# connector_schematic-3.net
KiCad netlist of a schematic drawn in EAGLE
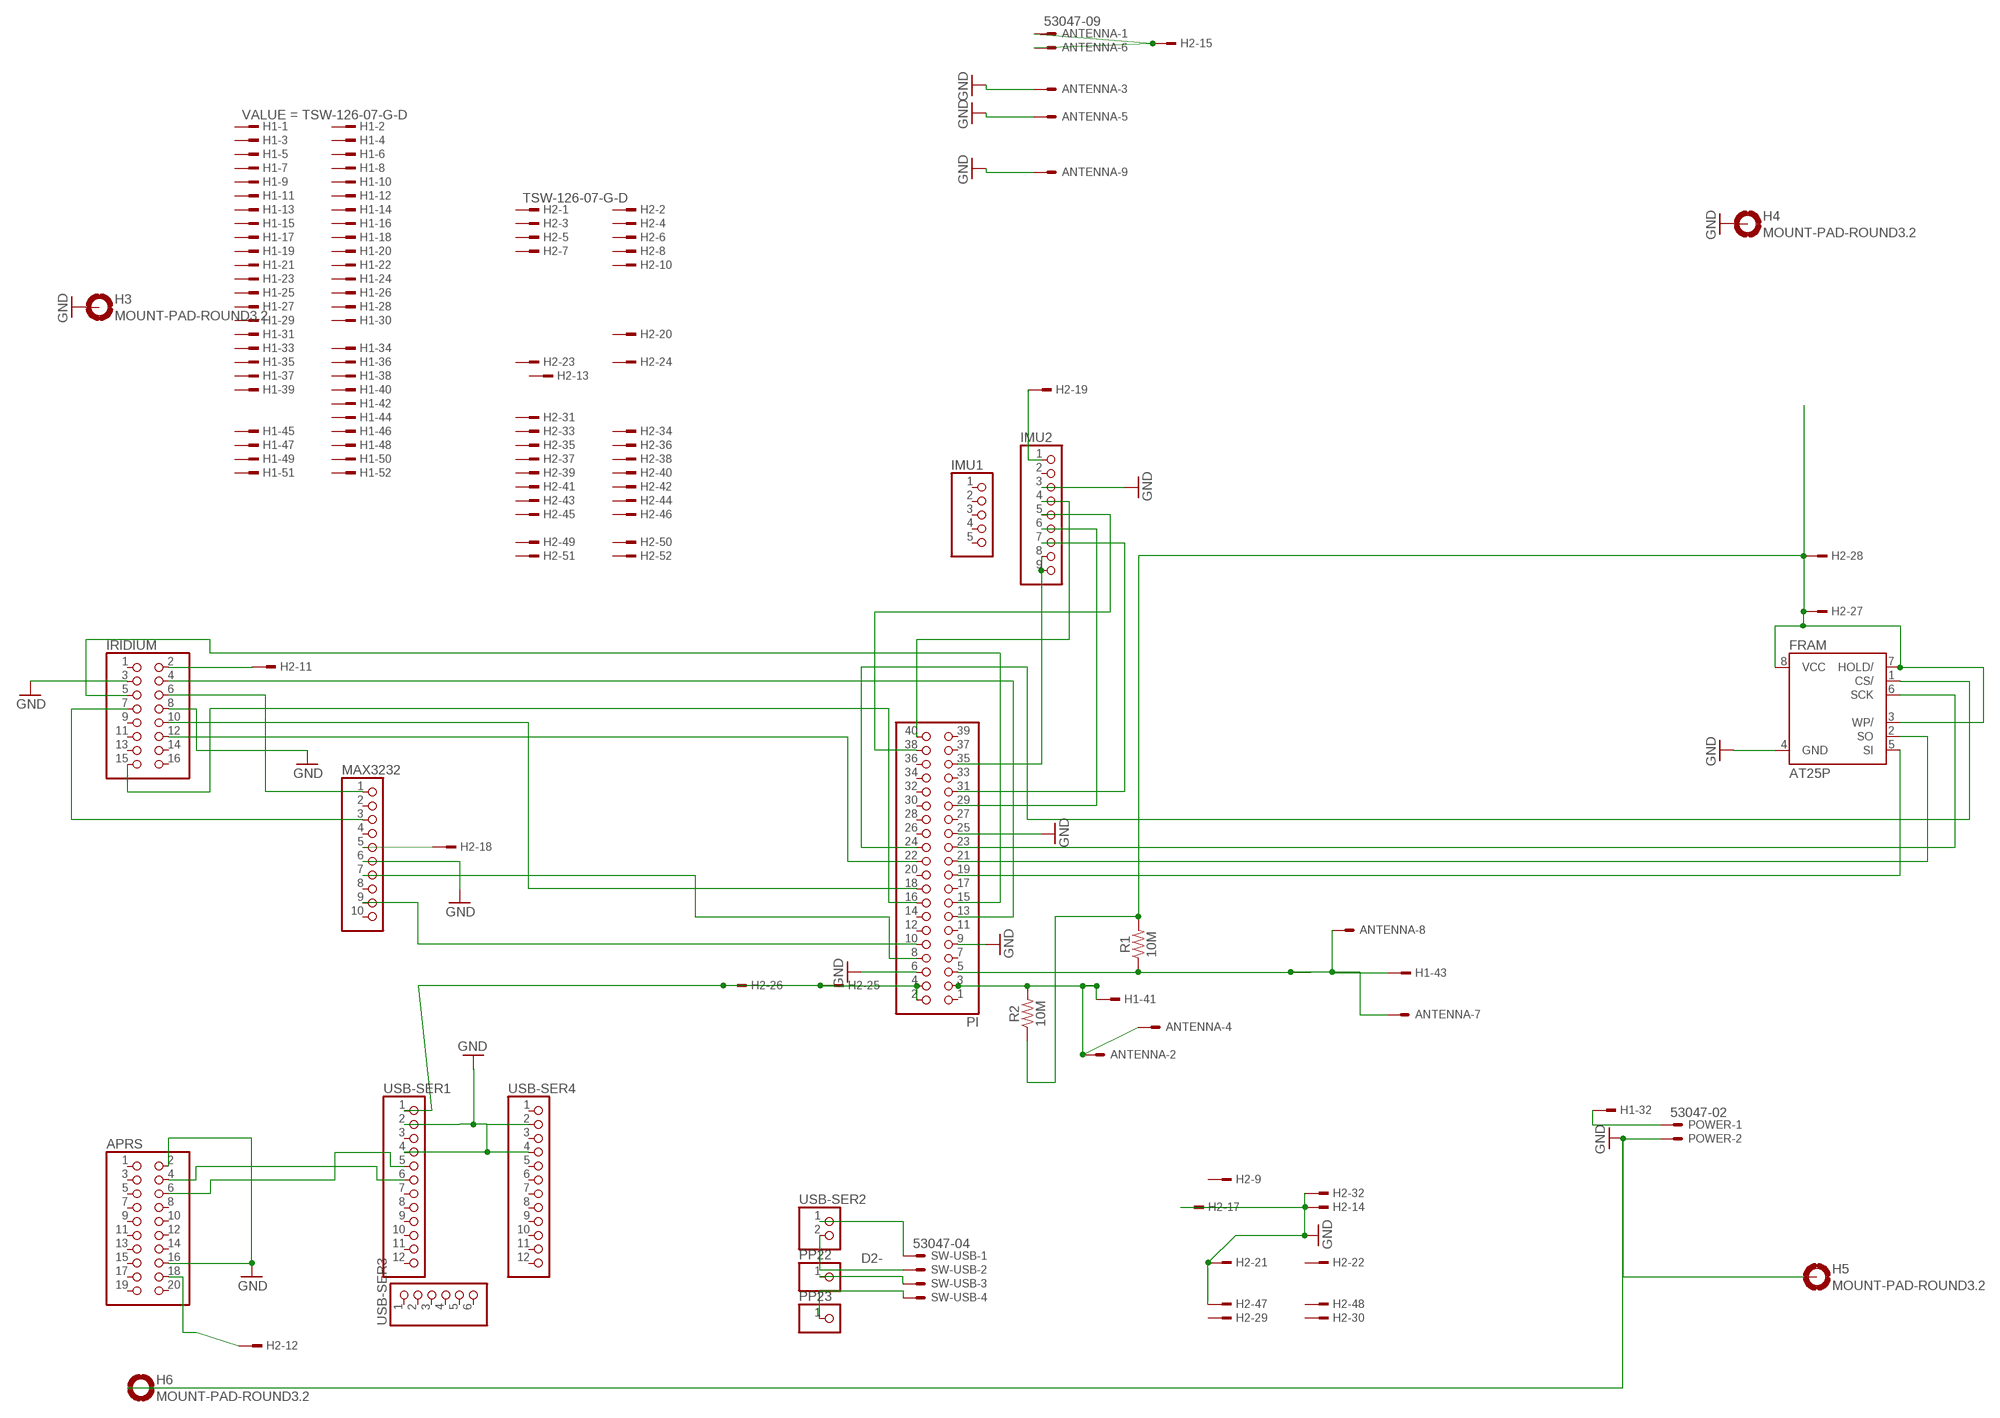
[diagram p0: schematic, sheet 1]

(export (version "E")
  (design (tool "Eeschema 10.0.6"))
  (components
    (comp (ref "ANTENNA")
      (value "53047-09")
      (footprint "eagle-import:53047-09")
      (fields (field (name "MF") "MOLEX") (field (name "MPN") "53047-0910"))
      (libsource (lib "eagle-import") (part "53?-09047"))
    )
    (comp (ref "APRS")
      (value "PINHD-2X10")
      (footprint "eagle-import:2X10")
      (libsource (lib "eagle-import") (part "PINHD-2X10"))
    )
    (comp (ref "FRAM")
      (value "AT25P")
      (footprint "eagle-import:DIL08")
      (fields (field (name "MPN") "CAT25040LI-G"))
      (libsource (lib "eagle-import") (part "AT25P"))
    )
    (comp (ref "H1")
      (value "TSW-126-07-G-D")
      (footprint "eagle-import:TSW-126-XX-G-D")
      (fields (field (name "MF") "Samtec Inc."))
      (libsource (lib "eagle-import") (part "TSW-126--G-D07"))
    )
    (comp (ref "H2")
      (value "TSW-126-07-G-D")
      (footprint "eagle-import:TSW-126-XX-G-D")
      (fields (field (name "MF") "Samtec Inc."))
      (libsource (lib "eagle-import") (part "TSW-126--G-D07"))
    )
    (comp (ref "H3")
      (value "MOUNT-PAD-ROUND3.2")
      (footprint "eagle-import:3,2-PAD")
      (libsource (lib "eagle-import") (part "MOUNT-PAD-ROUND3.2"))
    )
    (comp (ref "H4")
      (value "MOUNT-PAD-ROUND3.2")
      (footprint "eagle-import:3,2-PAD")
      (libsource (lib "eagle-import") (part "MOUNT-PAD-ROUND3.2"))
    )
    (comp (ref "H5")
      (value "MOUNT-PAD-ROUND3.2")
      (footprint "eagle-import:3,2-PAD")
      (libsource (lib "eagle-import") (part "MOUNT-PAD-ROUND3.2"))
    )
    (comp (ref "H6")
      (value "MOUNT-PAD-ROUND3.2")
      (footprint "eagle-import:3,2-PAD")
      (libsource (lib "eagle-import") (part "MOUNT-PAD-ROUND3.2"))
    )
    (comp (ref "IMU1")
      (value "PINHD-1X5")
      (footprint "eagle-import:1X05")
      (libsource (lib "eagle-import") (part "PINHD-1X5"))
    )
    (comp (ref "IMU2")
      (value "PINHD-1X9")
      (footprint "eagle-import:1X09")
      (libsource (lib "eagle-import") (part "PINHD-1X9"))
    )
    (comp (ref "IRIDIUM")
      (value "PINHD-2X8")
      (footprint "eagle-import:2X08")
      (libsource (lib "eagle-import") (part "PINHD-2X8"))
    )
    (comp (ref "MAX3232")
      (value "PINHD-1X10")
      (footprint "eagle-import:1X10")
      (libsource (lib "eagle-import") (part "PINHD-1X10"))
    )
    (comp (ref "PI")
      (value "PINHD-2X20")
      (footprint "eagle-import:2X20")
      (libsource (lib "eagle-import") (part "PINHD-2X20"))
    )
    (comp (ref "POWER")
      (value "53047-02")
      (footprint "eagle-import:53047-02")
      (fields (field (name "MF") "MOLEX") (field (name "MPN") "53047-0210"))
      (libsource (lib "eagle-import") (part "53?-02047"))
    )
    (comp (ref "PP22")
      (value "PINHD-1X1")
      (footprint "eagle-import:1X01")
      (libsource (lib "eagle-import") (part "PINHD-1X1"))
    )
    (comp (ref "PP23")
      (value "PINHD-1X1")
      (footprint "eagle-import:1X01")
      (libsource (lib "eagle-import") (part "PINHD-1X1"))
    )
    (comp (ref "R1")
      (value "10M")
      (footprint "eagle-import:AXIAL-0.3")
      (libsource (lib "eagle-import") (part "10MOHM-HORIZ-1/4W-5%"))
    )
    (comp (ref "R2")
      (value "10M")
      (footprint "eagle-import:AXIAL-0.3")
      (libsource (lib "eagle-import") (part "10MOHM-HORIZ-1/4W-5%"))
    )
    (comp (ref "SW-USB")
      (value "53047-04")
      (footprint "eagle-import:53047-04")
      (fields (field (name "MF") "WALDOM/MOLEX") (field (name "MPN") "53047-0410"))
      (libsource (lib "eagle-import") (part "53?-04047"))
    )
    (comp (ref "USB-SER1")
      (value "PINHD-1X12")
      (footprint "eagle-import:1X12")
      (libsource (lib "eagle-import") (part "PINHD-1X12"))
    )
    (comp (ref "USB-SER2")
      (value "PINHD-1X2")
      (footprint "eagle-import:1X02")
      (libsource (lib "eagle-import") (part "PINHD-1X2"))
    )
    (comp (ref "USB-SER3")
      (value "PINHD-1X6")
      (footprint "eagle-import:1X06")
      (libsource (lib "eagle-import") (part "PINHD-1X6"))
    )
    (comp (ref "USB-SER4")
      (value "PINHD-1X12")
      (footprint "eagle-import:1X12")
      (libsource (lib "eagle-import") (part "PINHD-1X12"))
    )
  )
  (nets
    (net (code "1") (name "/D2-") (class "Default")
      (node (ref "SW-USB") (pin "2") (pinfunction "S_2") (pintype "passive"))
      (node (ref "USB-SER2") (pin "2") (pinfunction "2_2") (pintype "passive"))
    )
    (net (code "2") (name "GND") (class "Default")
      (node (ref "ANTENNA") (pin "3") (pinfunction "S_3") (pintype "passive"))
      (node (ref "ANTENNA") (pin "5") (pinfunction "S_5") (pintype "passive"))
      (node (ref "ANTENNA") (pin "9") (pinfunction "S_9") (pintype "passive"))
      (node (ref "APRS") (pin "16") (pinfunction "16_16") (pintype "passive"))
      (node (ref "APRS") (pin "2") (pinfunction "2_2") (pintype "passive"))
      (node (ref "FRAM") (pin "4") (pinfunction "GND_4") (pintype "power_in"))
      (node (ref "H2") (pin "14") (pinfunction "1_14") (pintype "passive"))
      (node (ref "H2") (pin "17") (pinfunction "1_17") (pintype "passive"))
      (node (ref "H2") (pin "21") (pinfunction "1_21") (pintype "passive"))
      (node (ref "H2") (pin "32") (pinfunction "1_32") (pintype "passive"))
      (node (ref "H2") (pin "47") (pinfunction "1_47") (pintype "passive"))
      (node (ref "H3") (pin "B3,2") (pinfunction "MOUNT_B3,2") (pintype "passive"))
      (node (ref "H4") (pin "B3,2") (pinfunction "MOUNT_B3,2") (pintype "passive"))
      (node (ref "H5") (pin "B3,2") (pinfunction "MOUNT_B3,2") (pintype "passive"))
      (node (ref "H6") (pin "B3,2") (pinfunction "MOUNT_B3,2") (pintype "passive"))
      (node (ref "IMU2") (pin "3") (pinfunction "3_3") (pintype "passive"))
      (node (ref "IRIDIUM") (pin "3") (pinfunction "3_3") (pintype "passive"))
      (node (ref "IRIDIUM") (pin "8") (pinfunction "8_8") (pintype "passive"))
      (node (ref "MAX3232") (pin "6") (pinfunction "6_6") (pintype "passive"))
      (node (ref "PI") (pin "25") (pinfunction "25_25") (pintype "passive"))
      (node (ref "PI") (pin "6") (pinfunction "6_6") (pintype "passive"))
      (node (ref "PI") (pin "9") (pinfunction "9_9") (pintype "passive"))
      (node (ref "POWER") (pin "2") (pinfunction "S_2") (pintype "passive"))
      (node (ref "USB-SER1") (pin "2") (pinfunction "2_2") (pintype "passive"))
      (node (ref "USB-SER1") (pin "4") (pinfunction "4_4") (pintype "passive"))
      (node (ref "USB-SER4") (pin "2") (pinfunction "2_2") (pintype "passive"))
      (node (ref "USB-SER4") (pin "4") (pinfunction "4_4") (pintype "passive"))
    )
    (net (code "3") (name "Net-(ANTENNAA-S)") (class "Default")
      (node (ref "ANTENNA") (pin "1") (pinfunction "S_1") (pintype "passive"))
      (node (ref "ANTENNA") (pin "6") (pinfunction "S_6") (pintype "passive"))
      (node (ref "H2") (pin "15") (pinfunction "1_15") (pintype "passive"))
    )
    (net (code "4") (name "Net-(ANTENNAB-S)") (class "Default")
      (node (ref "ANTENNA") (pin "2") (pinfunction "S_2") (pintype "passive"))
      (node (ref "ANTENNA") (pin "4") (pinfunction "S_4") (pintype "passive"))
      (node (ref "H1") (pin "41") (pinfunction "1_41") (pintype "passive"))
      (node (ref "PI") (pin "3") (pinfunction "3_3") (pintype "passive"))
      (node (ref "R2") (pin "P$2") (pinfunction "2_P$2") (pintype "passive"))
    )
    (net (code "5") (name "Net-(ANTENNAG-S)") (class "Default")
      (node (ref "ANTENNA") (pin "7") (pinfunction "S_7") (pintype "passive"))
      (node (ref "ANTENNA") (pin "8") (pinfunction "S_8") (pintype "passive"))
      (node (ref "H1") (pin "43") (pinfunction "1_43") (pintype "passive"))
      (node (ref "PI") (pin "5") (pinfunction "5_5") (pintype "passive"))
      (node (ref "R1") (pin "P$1") (pinfunction "1_P$1") (pintype "passive"))
    )
    (net (code "6") (name "Net-(APRS-Pad4)") (class "Default")
      (node (ref "APRS") (pin "4") (pinfunction "4_4") (pintype "passive"))
      (node (ref "USB-SER1") (pin "6") (pinfunction "6_6") (pintype "passive"))
    )
    (net (code "7") (name "Net-(APRS-Pad6)") (class "Default")
      (node (ref "APRS") (pin "6") (pinfunction "6_6") (pintype "passive"))
      (node (ref "USB-SER1") (pin "5") (pinfunction "5_5") (pintype "passive"))
    )
    (net (code "8") (name "Net-(FRAM-CS{slash})") (class "Default")
      (node (ref "FRAM") (pin "1") (pinfunction "CS/_1") (pintype "input"))
      (node (ref "PI") (pin "24") (pinfunction "24_24") (pintype "passive"))
    )
    (net (code "9") (name "Net-(FRAM-HOLD{slash})") (class "Default")
      (node (ref "FRAM") (pin "3") (pinfunction "WP/_3") (pintype "input"))
      (node (ref "FRAM") (pin "7") (pinfunction "HOLD/_7") (pintype "input"))
      (node (ref "FRAM") (pin "8") (pinfunction "VCC_8") (pintype "power_in"))
      (node (ref "H2") (pin "27") (pinfunction "1_27") (pintype "passive"))
      (node (ref "H2") (pin "28") (pinfunction "1_28") (pintype "passive"))
      (node (ref "R1") (pin "P$2") (pinfunction "2_P$2") (pintype "passive"))
      (node (ref "R2") (pin "P$1") (pinfunction "1_P$1") (pintype "passive"))
    )
    (net (code "10") (name "Net-(FRAM-SCK)") (class "Default")
      (node (ref "FRAM") (pin "6") (pinfunction "SCK_6") (pintype "bidirectional"))
      (node (ref "PI") (pin "23") (pinfunction "23_23") (pintype "passive"))
    )
    (net (code "11") (name "Net-(FRAM-SI)") (class "Default")
      (node (ref "FRAM") (pin "5") (pinfunction "SI_5") (pintype "bidirectional"))
      (node (ref "PI") (pin "19") (pinfunction "19_19") (pintype "passive"))
    )
    (net (code "12") (name "Net-(FRAM-SO)") (class "Default")
      (node (ref "FRAM") (pin "2") (pinfunction "SO_2") (pintype "input"))
      (node (ref "PI") (pin "21") (pinfunction "21_21") (pintype "passive"))
    )
    (net (code "13") (name "Net-(H1Z-1)") (class "Default")
      (node (ref "H1") (pin "32") (pinfunction "1_32") (pintype "passive"))
      (node (ref "POWER") (pin "1") (pinfunction "S_1") (pintype "passive"))
    )
    (net (code "14") (name "Net-(H2C-1)") (class "Default")
      (node (ref "H2") (pin "11") (pinfunction "1_11") (pintype "passive"))
      (node (ref "IRIDIUM") (pin "2") (pinfunction "2_2") (pintype "passive"))
    )
    (net (code "15") (name "Net-(H2D-1)") (class "Default")
      (node (ref "APRS") (pin "18") (pinfunction "18_18") (pintype "passive"))
      (node (ref "H2") (pin "12") (pinfunction "1_12") (pintype "passive"))
    )
    (net (code "16") (name "Net-(H2J-1)") (class "Default")
      (node (ref "H2") (pin "18") (pinfunction "1_18") (pintype "passive"))
      (node (ref "MAX3232") (pin "5") (pinfunction "5_5") (pintype "passive"))
    )
    (net (code "17") (name "Net-(H2K-1)") (class "Default")
      (node (ref "H2") (pin "19") (pinfunction "1_19") (pintype "passive"))
      (node (ref "IMU2") (pin "1") (pinfunction "1_1") (pintype "passive"))
    )
    (net (code "18") (name "Net-(H2R-1)") (class "Default")
      (node (ref "H2") (pin "25") (pinfunction "1_25") (pintype "passive"))
      (node (ref "H2") (pin "26") (pinfunction "1_26") (pintype "passive"))
      (node (ref "PI") (pin "2") (pinfunction "2_2") (pintype "passive"))
      (node (ref "PI") (pin "4") (pinfunction "4_4") (pintype "passive"))
      (node (ref "USB-SER1") (pin "1") (pinfunction "1_1") (pintype "passive"))
    )
    (net (code "19") (name "Net-(IMU2-Pad4)") (class "Default")
      (node (ref "IMU2") (pin "4") (pinfunction "4_4") (pintype "passive"))
      (node (ref "PI") (pin "40") (pinfunction "40_40") (pintype "passive"))
    )
    (net (code "20") (name "Net-(IMU2-Pad5)") (class "Default")
      (node (ref "IMU2") (pin "5") (pinfunction "5_5") (pintype "passive"))
      (node (ref "PI") (pin "38") (pinfunction "38_38") (pintype "passive"))
    )
    (net (code "21") (name "Net-(IMU2-Pad6)") (class "Default")
      (node (ref "IMU2") (pin "6") (pinfunction "6_6") (pintype "passive"))
      (node (ref "PI") (pin "29") (pinfunction "29_29") (pintype "passive"))
    )
    (net (code "22") (name "Net-(IMU2-Pad7)") (class "Default")
      (node (ref "IMU2") (pin "7") (pinfunction "7_7") (pintype "passive"))
      (node (ref "PI") (pin "31") (pinfunction "31_31") (pintype "passive"))
    )
    (net (code "23") (name "Net-(IMU2-Pad8)") (class "Default")
      (node (ref "IMU2") (pin "8") (pinfunction "8_8") (pintype "passive"))
      (node (ref "IMU2") (pin "9") (pinfunction "9_9") (pintype "passive"))
      (node (ref "PI") (pin "35") (pinfunction "35_35") (pintype "passive"))
    )
    (net (code "24") (name "Net-(IRIDIUM-Pad4)") (class "Default")
      (node (ref "IRIDIUM") (pin "4") (pinfunction "4_4") (pintype "passive"))
      (node (ref "PI") (pin "13") (pinfunction "13_13") (pintype "passive"))
    )
    (net (code "25") (name "Net-(IRIDIUM-Pad5)") (class "Default")
      (node (ref "IRIDIUM") (pin "5") (pinfunction "5_5") (pintype "passive"))
      (node (ref "PI") (pin "15") (pinfunction "15_15") (pintype "passive"))
    )
    (net (code "26") (name "Net-(IRIDIUM-Pad6)") (class "Default")
      (node (ref "IRIDIUM") (pin "6") (pinfunction "6_6") (pintype "passive"))
      (node (ref "MAX3232") (pin "1") (pinfunction "1_1") (pintype "passive"))
    )
    (net (code "27") (name "Net-(IRIDIUM-Pad7)") (class "Default")
      (node (ref "IRIDIUM") (pin "7") (pinfunction "7_7") (pintype "passive"))
      (node (ref "MAX3232") (pin "3") (pinfunction "3_3") (pintype "passive"))
    )
    (net (code "28") (name "Net-(IRIDIUM-Pad10)") (class "Default")
      (node (ref "IRIDIUM") (pin "10") (pinfunction "10_10") (pintype "passive"))
      (node (ref "PI") (pin "18") (pinfunction "18_18") (pintype "passive"))
    )
    (net (code "29") (name "Net-(IRIDIUM-Pad12)") (class "Default")
      (node (ref "IRIDIUM") (pin "12") (pinfunction "12_12") (pintype "passive"))
      (node (ref "PI") (pin "22") (pinfunction "22_22") (pintype "passive"))
    )
    (net (code "30") (name "Net-(IRIDIUM-Pad15)") (class "Default")
      (node (ref "IRIDIUM") (pin "15") (pinfunction "15_15") (pintype "passive"))
      (node (ref "PI") (pin "16") (pinfunction "16_16") (pintype "passive"))
    )
    (net (code "31") (name "Net-(MAX3232-Pad7)") (class "Default")
      (node (ref "MAX3232") (pin "7") (pinfunction "7_7") (pintype "passive"))
      (node (ref "PI") (pin "8") (pinfunction "8_8") (pintype "passive"))
    )
    (net (code "32") (name "Net-(MAX3232-Pad9)") (class "Default")
      (node (ref "MAX3232") (pin "9") (pinfunction "9_9") (pintype "passive"))
      (node (ref "PI") (pin "10") (pinfunction "10_10") (pintype "passive"))
    )
    (net (code "33") (name "Net-(SW-USBA-S)") (class "Default")
      (node (ref "SW-USB") (pin "1") (pinfunction "S_1") (pintype "passive"))
      (node (ref "USB-SER2") (pin "1") (pinfunction "1_1") (pintype "passive"))
    )
    (net (code "34") (name "Net-(SW-USBC-S)") (class "Default")
      (node (ref "PP22") (pin "1") (pinfunction "1_1") (pintype "passive"))
      (node (ref "SW-USB") (pin "3") (pinfunction "S_3") (pintype "passive"))
    )
    (net (code "35") (name "Net-(SW-USBD-S)") (class "Default")
      (node (ref "PP23") (pin "1") (pinfunction "1_1") (pintype "passive"))
      (node (ref "SW-USB") (pin "4") (pinfunction "S_4") (pintype "passive"))
    )
    (net (code "36") (name "unconnected-(APRS-Pad1)") (class "Default")
      (node (ref "APRS") (pin "1") (pinfunction "1_1") (pintype "passive"))
    )
    (net (code "37") (name "unconnected-(APRS-Pad3)") (class "Default")
      (node (ref "APRS") (pin "3") (pinfunction "3_3") (pintype "passive"))
    )
    (net (code "38") (name "unconnected-(APRS-Pad5)") (class "Default")
      (node (ref "APRS") (pin "5") (pinfunction "5_5") (pintype "passive"))
    )
    (net (code "39") (name "unconnected-(APRS-Pad7)") (class "Default")
      (node (ref "APRS") (pin "7") (pinfunction "7_7") (pintype "passive"))
    )
    (net (code "40") (name "unconnected-(APRS-Pad8)") (class "Default")
      (node (ref "APRS") (pin "8") (pinfunction "8_8") (pintype "passive"))
    )
    (net (code "41") (name "unconnected-(APRS-Pad9)") (class "Default")
      (node (ref "APRS") (pin "9") (pinfunction "9_9") (pintype "passive"))
    )
    (net (code "42") (name "unconnected-(APRS-Pad10)") (class "Default")
      (node (ref "APRS") (pin "10") (pinfunction "10_10") (pintype "passive"))
    )
    (net (code "43") (name "unconnected-(APRS-Pad11)") (class "Default")
      (node (ref "APRS") (pin "11") (pinfunction "11_11") (pintype "passive"))
    )
    (net (code "44") (name "unconnected-(APRS-Pad12)") (class "Default")
      (node (ref "APRS") (pin "12") (pinfunction "12_12") (pintype "passive"))
    )
    (net (code "45") (name "unconnected-(APRS-Pad13)") (class "Default")
      (node (ref "APRS") (pin "13") (pinfunction "13_13") (pintype "passive"))
    )
    (net (code "46") (name "unconnected-(APRS-Pad14)") (class "Default")
      (node (ref "APRS") (pin "14") (pinfunction "14_14") (pintype "passive"))
    )
    (net (code "47") (name "unconnected-(APRS-Pad15)") (class "Default")
      (node (ref "APRS") (pin "15") (pinfunction "15_15") (pintype "passive"))
    )
    (net (code "48") (name "unconnected-(APRS-Pad17)") (class "Default")
      (node (ref "APRS") (pin "17") (pinfunction "17_17") (pintype "passive"))
    )
    (net (code "49") (name "unconnected-(APRS-Pad19)") (class "Default")
      (node (ref "APRS") (pin "19") (pinfunction "19_19") (pintype "passive"))
    )
    (net (code "50") (name "unconnected-(APRS-Pad20)") (class "Default")
      (node (ref "APRS") (pin "20") (pinfunction "20_20") (pintype "passive"))
    )
    (net (code "51") (name "unconnected-(H1-Pad1)") (class "Default")
      (node (ref "H1") (pin "1") (pinfunction "1_1") (pintype "passive"))
    )
    (net (code "52") (name "unconnected-(H1AA-1-Pad33)") (class "Default")
      (node (ref "H1") (pin "33") (pinfunction "1_33") (pintype "passive"))
    )
    (net (code "53") (name "unconnected-(H1AB-1-Pad34)") (class "Default")
      (node (ref "H1") (pin "34") (pinfunction "1_34") (pintype "passive"))
    )
    (net (code "54") (name "unconnected-(H1AC-1-Pad35)") (class "Default")
      (node (ref "H1") (pin "35") (pinfunction "1_35") (pintype "passive"))
    )
    (net (code "55") (name "unconnected-(H1AD-1-Pad36)") (class "Default")
      (node (ref "H1") (pin "36") (pinfunction "1_36") (pintype "passive"))
    )
    (net (code "56") (name "unconnected-(H1AE-1-Pad37)") (class "Default")
      (node (ref "H1") (pin "37") (pinfunction "1_37") (pintype "passive"))
    )
    (net (code "57") (name "unconnected-(H1AF-1-Pad38)") (class "Default")
      (node (ref "H1") (pin "38") (pinfunction "1_38") (pintype "passive"))
    )
    (net (code "58") (name "unconnected-(H1AG-1-Pad39)") (class "Default")
      (node (ref "H1") (pin "39") (pinfunction "1_39") (pintype "passive"))
    )
    (net (code "59") (name "unconnected-(H1AH-1-Pad4)") (class "Default")
      (node (ref "H1") (pin "4") (pinfunction "1_4") (pintype "passive"))
    )
    (net (code "60") (name "unconnected-(H1AI-1-Pad40)") (class "Default")
      (node (ref "H1") (pin "40") (pinfunction "1_40") (pintype "passive"))
    )
    (net (code "61") (name "unconnected-(H1AK-1-Pad42)") (class "Default")
      (node (ref "H1") (pin "42") (pinfunction "1_42") (pintype "passive"))
    )
    (net (code "62") (name "unconnected-(H1AM-1-Pad44)") (class "Default")
      (node (ref "H1") (pin "44") (pinfunction "1_44") (pintype "passive"))
    )
    (net (code "63") (name "unconnected-(H1AN-1-Pad45)") (class "Default")
      (node (ref "H1") (pin "45") (pinfunction "1_45") (pintype "passive"))
    )
    (net (code "64") (name "unconnected-(H1AO-1-Pad46)") (class "Default")
      (node (ref "H1") (pin "46") (pinfunction "1_46") (pintype "passive"))
    )
    (net (code "65") (name "unconnected-(H1AP-1-Pad47)") (class "Default")
      (node (ref "H1") (pin "47") (pinfunction "1_47") (pintype "passive"))
    )
    (net (code "66") (name "unconnected-(H1AQ-1-Pad48)") (class "Default")
      (node (ref "H1") (pin "48") (pinfunction "1_48") (pintype "passive"))
    )
    (net (code "67") (name "unconnected-(H1AR-1-Pad49)") (class "Default")
      (node (ref "H1") (pin "49") (pinfunction "1_49") (pintype "passive"))
    )
    (net (code "68") (name "unconnected-(H1AS-1-Pad5)") (class "Default")
      (node (ref "H1") (pin "5") (pinfunction "1_5") (pintype "passive"))
    )
    (net (code "69") (name "unconnected-(H1AT-1-Pad50)") (class "Default")
      (node (ref "H1") (pin "50") (pinfunction "1_50") (pintype "passive"))
    )
    (net (code "70") (name "unconnected-(H1AU-1-Pad51)") (class "Default")
      (node (ref "H1") (pin "51") (pinfunction "1_51") (pintype "passive"))
    )
    (net (code "71") (name "unconnected-(H1AV-1-Pad52)") (class "Default")
      (node (ref "H1") (pin "52") (pinfunction "1_52") (pintype "passive"))
    )
    (net (code "72") (name "unconnected-(H1AW-1-Pad6)") (class "Default")
      (node (ref "H1") (pin "6") (pinfunction "1_6") (pintype "passive"))
    )
    (net (code "73") (name "unconnected-(H1AX-1-Pad7)") (class "Default")
      (node (ref "H1") (pin "7") (pinfunction "1_7") (pintype "passive"))
    )
    (net (code "74") (name "unconnected-(H1AY-1-Pad8)") (class "Default")
      (node (ref "H1") (pin "8") (pinfunction "1_8") (pintype "passive"))
    )
    (net (code "75") (name "unconnected-(H1AZ-1-Pad9)") (class "Default")
      (node (ref "H1") (pin "9") (pinfunction "1_9") (pintype "passive"))
    )
    (net (code "76") (name "unconnected-(H1B-1-Pad10)") (class "Default")
      (node (ref "H1") (pin "10") (pinfunction "1_10") (pintype "passive"))
    )
    (net (code "77") (name "unconnected-(H1C-1-Pad11)") (class "Default")
      (node (ref "H1") (pin "11") (pinfunction "1_11") (pintype "passive"))
    )
    (net (code "78") (name "unconnected-(H1D-1-Pad12)") (class "Default")
      (node (ref "H1") (pin "12") (pinfunction "1_12") (pintype "passive"))
    )
    (net (code "79") (name "unconnected-(H1E-1-Pad13)") (class "Default")
      (node (ref "H1") (pin "13") (pinfunction "1_13") (pintype "passive"))
    )
    (net (code "80") (name "unconnected-(H1F-1-Pad14)") (class "Default")
      (node (ref "H1") (pin "14") (pinfunction "1_14") (pintype "passive"))
    )
    (net (code "81") (name "unconnected-(H1G-1-Pad15)") (class "Default")
      (node (ref "H1") (pin "15") (pinfunction "1_15") (pintype "passive"))
    )
    (net (code "82") (name "unconnected-(H1H-1-Pad16)") (class "Default")
      (node (ref "H1") (pin "16") (pinfunction "1_16") (pintype "passive"))
    )
    (net (code "83") (name "unconnected-(H1I-1-Pad17)") (class "Default")
      (node (ref "H1") (pin "17") (pinfunction "1_17") (pintype "passive"))
    )
    (net (code "84") (name "unconnected-(H1J-1-Pad18)") (class "Default")
      (node (ref "H1") (pin "18") (pinfunction "1_18") (pintype "passive"))
    )
    (net (code "85") (name "unconnected-(H1K-1-Pad19)") (class "Default")
      (node (ref "H1") (pin "19") (pinfunction "1_19") (pintype "passive"))
    )
    (net (code "86") (name "unconnected-(H1L-1-Pad2)") (class "Default")
      (node (ref "H1") (pin "2") (pinfunction "1_2") (pintype "passive"))
    )
    (net (code "87") (name "unconnected-(H1M-1-Pad20)") (class "Default")
      (node (ref "H1") (pin "20") (pinfunction "1_20") (pintype "passive"))
    )
    (net (code "88") (name "unconnected-(H1N-1-Pad21)") (class "Default")
      (node (ref "H1") (pin "21") (pinfunction "1_21") (pintype "passive"))
    )
    (net (code "89") (name "unconnected-(H1O-1-Pad22)") (class "Default")
      (node (ref "H1") (pin "22") (pinfunction "1_22") (pintype "passive"))
    )
    (net (code "90") (name "unconnected-(H1P-1-Pad23)") (class "Default")
      (node (ref "H1") (pin "23") (pinfunction "1_23") (pintype "passive"))
    )
    (net (code "91") (name "unconnected-(H1Q-1-Pad24)") (class "Default")
      (node (ref "H1") (pin "24") (pinfunction "1_24") (pintype "passive"))
    )
    (net (code "92") (name "unconnected-(H1R-1-Pad25)") (class "Default")
      (node (ref "H1") (pin "25") (pinfunction "1_25") (pintype "passive"))
    )
    (net (code "93") (name "unconnected-(H1S-1-Pad26)") (class "Default")
      (node (ref "H1") (pin "26") (pinfunction "1_26") (pintype "passive"))
    )
    (net (code "94") (name "unconnected-(H1T-1-Pad27)") (class "Default")
      (node (ref "H1") (pin "27") (pinfunction "1_27") (pintype "passive"))
    )
    (net (code "95") (name "unconnected-(H1U-1-Pad28)") (class "Default")
      (node (ref "H1") (pin "28") (pinfunction "1_28") (pintype "passive"))
    )
    (net (code "96") (name "unconnected-(H1V-1-Pad29)") (class "Default")
      (node (ref "H1") (pin "29") (pinfunction "1_29") (pintype "passive"))
    )
    (net (code "97") (name "unconnected-(H1W-1-Pad3)") (class "Default")
      (node (ref "H1") (pin "3") (pinfunction "1_3") (pintype "passive"))
    )
    (net (code "98") (name "unconnected-(H1X-1-Pad30)") (class "Default")
      (node (ref "H1") (pin "30") (pinfunction "1_30") (pintype "passive"))
    )
    (net (code "99") (name "unconnected-(H1Y-1-Pad31)") (class "Default")
      (node (ref "H1") (pin "31") (pinfunction "1_31") (pintype "passive"))
    )
    (net (code "100") (name "unconnected-(H2-Pad1)") (class "Default")
      (node (ref "H2") (pin "1") (pinfunction "1_1") (pintype "passive"))
    )
    (net (code "101") (name "unconnected-(H2AA-1-Pad33)") (class "Default")
      (node (ref "H2") (pin "33") (pinfunction "1_33") (pintype "passive"))
    )
    (net (code "102") (name "unconnected-(H2AB-1-Pad34)") (class "Default")
      (node (ref "H2") (pin "34") (pinfunction "1_34") (pintype "passive"))
    )
    (net (code "103") (name "unconnected-(H2AC-1-Pad35)") (class "Default")
      (node (ref "H2") (pin "35") (pinfunction "1_35") (pintype "passive"))
    )
    (net (code "104") (name "unconnected-(H2AD-1-Pad36)") (class "Default")
      (node (ref "H2") (pin "36") (pinfunction "1_36") (pintype "passive"))
    )
    (net (code "105") (name "unconnected-(H2AE-1-Pad37)") (class "Default")
      (node (ref "H2") (pin "37") (pinfunction "1_37") (pintype "passive"))
    )
    (net (code "106") (name "unconnected-(H2AF-1-Pad38)") (class "Default")
      (node (ref "H2") (pin "38") (pinfunction "1_38") (pintype "passive"))
    )
    (net (code "107") (name "unconnected-(H2AG-1-Pad39)") (class "Default")
      (node (ref "H2") (pin "39") (pinfunction "1_39") (pintype "passive"))
    )
    (net (code "108") (name "unconnected-(H2AH-1-Pad4)") (class "Default")
      (node (ref "H2") (pin "4") (pinfunction "1_4") (pintype "passive"))
    )
    (net (code "109") (name "unconnected-(H2AI-1-Pad40)") (class "Default")
      (node (ref "H2") (pin "40") (pinfunction "1_40") (pintype "passive"))
    )
    (net (code "110") (name "unconnected-(H2AJ-1-Pad41)") (class "Default")
      (node (ref "H2") (pin "41") (pinfunction "1_41") (pintype "passive"))
    )
    (net (code "111") (name "unconnected-(H2AK-1-Pad42)") (class "Default")
      (node (ref "H2") (pin "42") (pinfunction "1_42") (pintype "passive"))
    )
    (net (code "112") (name "unconnected-(H2AL-1-Pad43)") (class "Default")
      (node (ref "H2") (pin "43") (pinfunction "1_43") (pintype "passive"))
    )
    (net (code "113") (name "unconnected-(H2AM-1-Pad44)") (class "Default")
      (node (ref "H2") (pin "44") (pinfunction "1_44") (pintype "passive"))
    )
    (net (code "114") (name "unconnected-(H2AN-1-Pad45)") (class "Default")
      (node (ref "H2") (pin "45") (pinfunction "1_45") (pintype "passive"))
    )
    (net (code "115") (name "unconnected-(H2AO-1-Pad46)") (class "Default")
      (node (ref "H2") (pin "46") (pinfunction "1_46") (pintype "passive"))
    )
    (net (code "116") (name "unconnected-(H2AQ-1-Pad48)") (class "Default")
      (node (ref "H2") (pin "48") (pinfunction "1_48") (pintype "passive"))
    )
    (net (code "117") (name "unconnected-(H2AR-1-Pad49)") (class "Default")
      (node (ref "H2") (pin "49") (pinfunction "1_49") (pintype "passive"))
    )
    (net (code "118") (name "unconnected-(H2AS-1-Pad5)") (class "Default")
      (node (ref "H2") (pin "5") (pinfunction "1_5") (pintype "passive"))
    )
    (net (code "119") (name "unconnected-(H2AT-1-Pad50)") (class "Default")
      (node (ref "H2") (pin "50") (pinfunction "1_50") (pintype "passive"))
    )
    (net (code "120") (name "unconnected-(H2AU-1-Pad51)") (class "Default")
      (node (ref "H2") (pin "51") (pinfunction "1_51") (pintype "passive"))
    )
    (net (code "121") (name "unconnected-(H2AV-1-Pad52)") (class "Default")
      (node (ref "H2") (pin "52") (pinfunction "1_52") (pintype "passive"))
    )
    (net (code "122") (name "unconnected-(H2AW-1-Pad6)") (class "Default")
      (node (ref "H2") (pin "6") (pinfunction "1_6") (pintype "passive"))
    )
    (net (code "123") (name "unconnected-(H2AX-1-Pad7)") (class "Default")
      (node (ref "H2") (pin "7") (pinfunction "1_7") (pintype "passive"))
    )
    (net (code "124") (name "unconnected-(H2AY-1-Pad8)") (class "Default")
      (node (ref "H2") (pin "8") (pinfunction "1_8") (pintype "passive"))
    )
    (net (code "125") (name "unconnected-(H2AZ-1-Pad9)") (class "Default")
      (node (ref "H2") (pin "9") (pinfunction "1_9") (pintype "passive"))
    )
    (net (code "126") (name "unconnected-(H2B-1-Pad10)") (class "Default")
      (node (ref "H2") (pin "10") (pinfunction "1_10") (pintype "passive"))
    )
    (net (code "127") (name "unconnected-(H2E-1-Pad13)") (class "Default")
      (node (ref "H2") (pin "13") (pinfunction "1_13") (pintype "passive"))
    )
    (net (code "128") (name "unconnected-(H2L-1-Pad2)") (class "Default")
      (node (ref "H2") (pin "2") (pinfunction "1_2") (pintype "passive"))
    )
    (net (code "129") (name "unconnected-(H2M-1-Pad20)") (class "Default")
      (node (ref "H2") (pin "20") (pinfunction "1_20") (pintype "passive"))
    )
    (net (code "130") (name "unconnected-(H2O-1-Pad22)") (class "Default")
      (node (ref "H2") (pin "22") (pinfunction "1_22") (pintype "passive"))
    )
    (net (code "131") (name "unconnected-(H2P-1-Pad23)") (class "Default")
      (node (ref "H2") (pin "23") (pinfunction "1_23") (pintype "passive"))
    )
    (net (code "132") (name "unconnected-(H2Q-1-Pad24)") (class "Default")
      (node (ref "H2") (pin "24") (pinfunction "1_24") (pintype "passive"))
    )
    (net (code "133") (name "unconnected-(H2V-1-Pad29)") (class "Default")
      (node (ref "H2") (pin "29") (pinfunction "1_29") (pintype "passive"))
    )
    (net (code "134") (name "unconnected-(H2W-1-Pad3)") (class "Default")
      (node (ref "H2") (pin "3") (pinfunction "1_3") (pintype "passive"))
    )
    (net (code "135") (name "unconnected-(H2X-1-Pad30)") (class "Default")
      (node (ref "H2") (pin "30") (pinfunction "1_30") (pintype "passive"))
    )
    (net (code "136") (name "unconnected-(H2Y-1-Pad31)") (class "Default")
      (node (ref "H2") (pin "31") (pinfunction "1_31") (pintype "passive"))
    )
    (net (code "137") (name "unconnected-(IMU1-Pad1)") (class "Default")
      (node (ref "IMU1") (pin "1") (pinfunction "1_1") (pintype "passive"))
    )
    (net (code "138") (name "unconnected-(IMU1-Pad2)") (class "Default")
      (node (ref "IMU1") (pin "2") (pinfunction "2_2") (pintype "passive"))
    )
    (net (code "139") (name "unconnected-(IMU1-Pad3)") (class "Default")
      (node (ref "IMU1") (pin "3") (pinfunction "3_3") (pintype "passive"))
    )
    (net (code "140") (name "unconnected-(IMU1-Pad4)") (class "Default")
      (node (ref "IMU1") (pin "4") (pinfunction "4_4") (pintype "passive"))
    )
    (net (code "141") (name "unconnected-(IMU1-Pad5)") (class "Default")
      (node (ref "IMU1") (pin "5") (pinfunction "5_5") (pintype "passive"))
    )
    (net (code "142") (name "unconnected-(IMU2-Pad2)") (class "Default")
      (node (ref "IMU2") (pin "2") (pinfunction "2_2") (pintype "passive"))
    )
    (net (code "143") (name "unconnected-(IRIDIUM-Pad1)") (class "Default")
      (node (ref "IRIDIUM") (pin "1") (pinfunction "1_1") (pintype "passive"))
    )
    (net (code "144") (name "unconnected-(IRIDIUM-Pad9)") (class "Default")
      (node (ref "IRIDIUM") (pin "9") (pinfunction "9_9") (pintype "passive"))
    )
    (net (code "145") (name "unconnected-(IRIDIUM-Pad11)") (class "Default")
      (node (ref "IRIDIUM") (pin "11") (pinfunction "11_11") (pintype "passive"))
    )
    (net (code "146") (name "unconnected-(IRIDIUM-Pad13)") (class "Default")
      (node (ref "IRIDIUM") (pin "13") (pinfunction "13_13") (pintype "passive"))
    )
    (net (code "147") (name "unconnected-(IRIDIUM-Pad14)") (class "Default")
      (node (ref "IRIDIUM") (pin "14") (pinfunction "14_14") (pintype "passive"))
    )
    (net (code "148") (name "unconnected-(IRIDIUM-Pad16)") (class "Default")
      (node (ref "IRIDIUM") (pin "16") (pinfunction "16_16") (pintype "passive"))
    )
    (net (code "149") (name "unconnected-(MAX3232-Pad2)") (class "Default")
      (node (ref "MAX3232") (pin "2") (pinfunction "2_2") (pintype "passive"))
    )
    (net (code "150") (name "unconnected-(MAX3232-Pad4)") (class "Default")
      (node (ref "MAX3232") (pin "4") (pinfunction "4_4") (pintype "passive"))
    )
    (net (code "151") (name "unconnected-(MAX3232-Pad8)") (class "Default")
      (node (ref "MAX3232") (pin "8") (pinfunction "8_8") (pintype "passive"))
    )
    (net (code "152") (name "unconnected-(MAX3232-Pad10)") (class "Default")
      (node (ref "MAX3232") (pin "10") (pinfunction "10_10") (pintype "passive"))
    )
    (net (code "153") (name "unconnected-(PI-Pad1)") (class "Default")
      (node (ref "PI") (pin "1") (pinfunction "1_1") (pintype "passive"))
    )
    (net (code "154") (name "unconnected-(PI-Pad7)") (class "Default")
      (node (ref "PI") (pin "7") (pinfunction "7_7") (pintype "passive"))
    )
    (net (code "155") (name "unconnected-(PI-Pad11)") (class "Default")
      (node (ref "PI") (pin "11") (pinfunction "11_11") (pintype "passive"))
    )
    (net (code "156") (name "unconnected-(PI-Pad12)") (class "Default")
      (node (ref "PI") (pin "12") (pinfunction "12_12") (pintype "passive"))
    )
    (net (code "157") (name "unconnected-(PI-Pad14)") (class "Default")
      (node (ref "PI") (pin "14") (pinfunction "14_14") (pintype "passive"))
    )
    (net (code "158") (name "unconnected-(PI-Pad17)") (class "Default")
      (node (ref "PI") (pin "17") (pinfunction "17_17") (pintype "passive"))
    )
    (net (code "159") (name "unconnected-(PI-Pad20)") (class "Default")
      (node (ref "PI") (pin "20") (pinfunction "20_20") (pintype "passive"))
    )
    (net (code "160") (name "unconnected-(PI-Pad26)") (class "Default")
      (node (ref "PI") (pin "26") (pinfunction "26_26") (pintype "passive"))
    )
    (net (code "161") (name "unconnected-(PI-Pad27)") (class "Default")
      (node (ref "PI") (pin "27") (pinfunction "27_27") (pintype "passive"))
    )
    (net (code "162") (name "unconnected-(PI-Pad28)") (class "Default")
      (node (ref "PI") (pin "28") (pinfunction "28_28") (pintype "passive"))
    )
    (net (code "163") (name "unconnected-(PI-Pad30)") (class "Default")
      (node (ref "PI") (pin "30") (pinfunction "30_30") (pintype "passive"))
    )
    (net (code "164") (name "unconnected-(PI-Pad32)") (class "Default")
      (node (ref "PI") (pin "32") (pinfunction "32_32") (pintype "passive"))
    )
    (net (code "165") (name "unconnected-(PI-Pad33)") (class "Default")
      (node (ref "PI") (pin "33") (pinfunction "33_33") (pintype "passive"))
    )
    (net (code "166") (name "unconnected-(PI-Pad34)") (class "Default")
      (node (ref "PI") (pin "34") (pinfunction "34_34") (pintype "passive"))
    )
    (net (code "167") (name "unconnected-(PI-Pad36)") (class "Default")
      (node (ref "PI") (pin "36") (pinfunction "36_36") (pintype "passive"))
    )
    (net (code "168") (name "unconnected-(PI-Pad37)") (class "Default")
      (node (ref "PI") (pin "37") (pinfunction "37_37") (pintype "passive"))
    )
    (net (code "169") (name "unconnected-(PI-Pad39)") (class "Default")
      (node (ref "PI") (pin "39") (pinfunction "39_39") (pintype "passive"))
    )
    (net (code "170") (name "unconnected-(USB-SER1-Pad3)") (class "Default")
      (node (ref "USB-SER1") (pin "3") (pinfunction "3_3") (pintype "passive"))
    )
    (net (code "171") (name "unconnected-(USB-SER1-Pad7)") (class "Default")
      (node (ref "USB-SER1") (pin "7") (pinfunction "7_7") (pintype "passive"))
    )
    (net (code "172") (name "unconnected-(USB-SER1-Pad8)") (class "Default")
      (node (ref "USB-SER1") (pin "8") (pinfunction "8_8") (pintype "passive"))
    )
    (net (code "173") (name "unconnected-(USB-SER1-Pad9)") (class "Default")
      (node (ref "USB-SER1") (pin "9") (pinfunction "9_9") (pintype "passive"))
    )
    (net (code "174") (name "unconnected-(USB-SER1-Pad10)") (class "Default")
      (node (ref "USB-SER1") (pin "10") (pinfunction "10_10") (pintype "passive"))
    )
    (net (code "175") (name "unconnected-(USB-SER1-Pad11)") (class "Default")
      (node (ref "USB-SER1") (pin "11") (pinfunction "11_11") (pintype "passive"))
    )
    (net (code "176") (name "unconnected-(USB-SER1-Pad12)") (class "Default")
      (node (ref "USB-SER1") (pin "12") (pinfunction "12_12") (pintype "passive"))
    )
    (net (code "177") (name "unconnected-(USB-SER3-Pad1)") (class "Default")
      (node (ref "USB-SER3") (pin "1") (pinfunction "1_1") (pintype "passive"))
    )
    (net (code "178") (name "unconnected-(USB-SER3-Pad2)") (class "Default")
      (node (ref "USB-SER3") (pin "2") (pinfunction "2_2") (pintype "passive"))
    )
    (net (code "179") (name "unconnected-(USB-SER3-Pad3)") (class "Default")
      (node (ref "USB-SER3") (pin "3") (pinfunction "3_3") (pintype "passive"))
    )
    (net (code "180") (name "unconnected-(USB-SER3-Pad4)") (class "Default")
      (node (ref "USB-SER3") (pin "4") (pinfunction "4_4") (pintype "passive"))
    )
    (net (code "181") (name "unconnected-(USB-SER3-Pad5)") (class "Default")
      (node (ref "USB-SER3") (pin "5") (pinfunction "5_5") (pintype "passive"))
    )
    (net (code "182") (name "unconnected-(USB-SER3-Pad6)") (class "Default")
      (node (ref "USB-SER3") (pin "6") (pinfunction "6_6") (pintype "passive"))
    )
    (net (code "183") (name "unconnected-(USB-SER4-Pad1)") (class "Default")
      (node (ref "USB-SER4") (pin "1") (pinfunction "1_1") (pintype "passive"))
    )
    (net (code "184") (name "unconnected-(USB-SER4-Pad3)") (class "Default")
      (node (ref "USB-SER4") (pin "3") (pinfunction "3_3") (pintype "passive"))
    )
    (net (code "185") (name "unconnected-(USB-SER4-Pad5)") (class "Default")
      (node (ref "USB-SER4") (pin "5") (pinfunction "5_5") (pintype "passive"))
    )
    (net (code "186") (name "unconnected-(USB-SER4-Pad6)") (class "Default")
      (node (ref "USB-SER4") (pin "6") (pinfunction "6_6") (pintype "passive"))
    )
    (net (code "187") (name "unconnected-(USB-SER4-Pad7)") (class "Default")
      (node (ref "USB-SER4") (pin "7") (pinfunction "7_7") (pintype "passive"))
    )
    (net (code "188") (name "unconnected-(USB-SER4-Pad8)") (class "Default")
      (node (ref "USB-SER4") (pin "8") (pinfunction "8_8") (pintype "passive"))
    )
    (net (code "189") (name "unconnected-(USB-SER4-Pad9)") (class "Default")
      (node (ref "USB-SER4") (pin "9") (pinfunction "9_9") (pintype "passive"))
    )
    (net (code "190") (name "unconnected-(USB-SER4-Pad10)") (class "Default")
      (node (ref "USB-SER4") (pin "10") (pinfunction "10_10") (pintype "passive"))
    )
    (net (code "191") (name "unconnected-(USB-SER4-Pad11)") (class "Default")
      (node (ref "USB-SER4") (pin "11") (pinfunction "11_11") (pintype "passive"))
    )
    (net (code "192") (name "unconnected-(USB-SER4-Pad12)") (class "Default")
      (node (ref "USB-SER4") (pin "12") (pinfunction "12_12") (pintype "passive"))
    )
  )
)
